# Power.net
KiCad netlist of a schematic drawn in Altium Designer
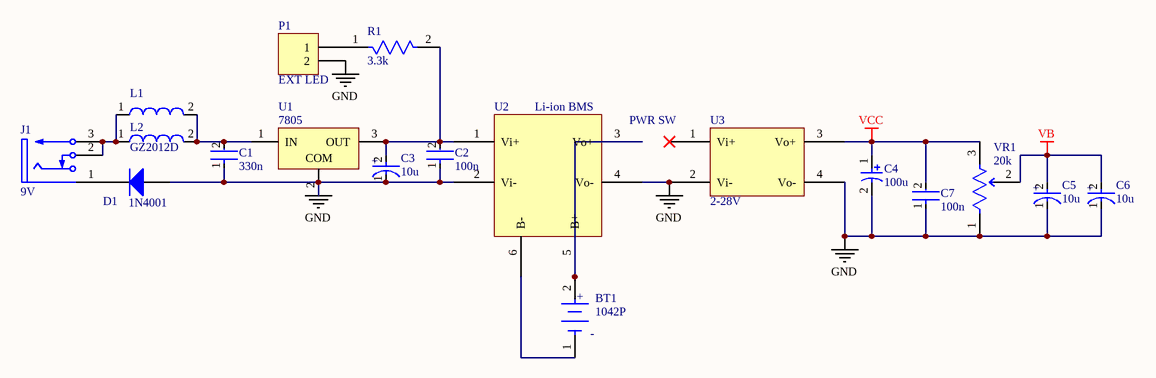
[diagram p0: Power.SchDoc]

(export (version "E")
  (design (tool "Eeschema 10.0.6"))
  (components
    (comp (ref "BT1")
      (value "1042P")
      (footprint "FP-1042P-MFG")
      (description "BATTERY HOLDER 18650 SMD TAB")
      (libsource (lib "Altium Content Vault") (part "60d3b5b901a8747834971d0eb8cf3fd"))
    )
    (comp (ref "C1")
      (value "330n")
      (footprint "FP-CL10-IPC_A")
      (description "Cap Ceramic 1nF 50V C0G ±5% Pad SMD 0603 +125°C T/R")
      (fields (field (name "VOLTAGE") "50V") (field (name "TOLERANCE") "5%"))
      (libsource (lib "Altium Content Vault") (part "b4654b650e69147ec39a6b967a45e02"))
    )
    (comp (ref "C2")
      (value "100n")
      (footprint "FP-CL10-IPC_A")
      (description "Cap Ceramic 1nF 50V C0G ±5% Pad SMD 0603 +125°C T/R")
      (fields (field (name "VOLTAGE") "50V") (field (name "TOLERANCE") "5%"))
      (libsource (lib "Altium Content Vault") (part "b4654b650e69147ec39a6b967a45e02"))
    )
    (comp (ref "C3")
      (value "10u")
      (footprint "FP-TAJA-MFG")
      (description "10uF 16V  ±10% 3Ω 1206  SMD Tantalum Capacitor")
      (fields (field (name "VOLTAGE") "16V") (field (name "TOLERANCE") "10%"))
      (libsource (lib "Altium Content Vault") (part "203bc49f2ac43e59fd269a8c329ed05"))
    )
    (comp (ref "C4") (value "100u") (footprint "EL_5X11_RA") (libsource (lib "TH_Symbols") (part "CAP_POL")))
    (comp (ref "C5")
      (value "10u")
      (footprint "FP-TAJA-MFG")
      (description "10uF 16V  ±10% 3Ω 1206  SMD Tantalum Capacitor")
      (fields (field (name "VOLTAGE") "16V") (field (name "TOLERANCE") "10%"))
      (libsource (lib "Altium Content Vault") (part "203bc49f2ac43e59fd269a8c329ed05"))
    )
    (comp (ref "C6")
      (value "10u")
      (footprint "FP-TAJA-MFG")
      (description "10uF 16V  ±10% 3Ω 1206  SMD Tantalum Capacitor")
      (fields (field (name "VOLTAGE") "16V") (field (name "TOLERANCE") "10%"))
      (libsource (lib "Altium Content Vault") (part "203bc49f2ac43e59fd269a8c329ed05"))
    )
    (comp (ref "C7")
      (value "100n")
      (footprint "FP-CL10-IPC_A")
      (description "Cap Ceramic 1nF 50V C0G ±5% Pad SMD 0603 +125°C T/R")
      (fields (field (name "VOLTAGE") "50V") (field (name "TOLERANCE") "5%"))
      (libsource (lib "Altium Content Vault") (part "b4654b650e69147ec39a6b967a45e02"))
    )
    (comp (ref "D1") (value "1N4001") (footprint "DO-41") (libsource (lib "TH_Symbols") (part "DIODE_SW")))
    (comp (ref "J1")
      (value "9V")
      (footprint "SWITCH-RAPC712X-3_V")
      (description "Power Jack, 5 A, 3-Pin THD, RoHS, Bulk")
      (fields (field (name "MANUFACTURER") "Switchcraft"))
      (libsource (lib "Altium Content Vault") (part "SWITCH-RAPC712X-3"))
    )
    (comp (ref "L1")
      (value "GZ2012D")
      (footprint "SMD-0805")
      (description "SMD EMI Suppression Ferrite Bead WE-CBF, Z = 1000 Ohm")
      (libsource (lib "Altium Content Vault") (part "PAS-IND-INDUCTOR-2"))
    )
    (comp (ref "L2")
      (value "GZ2012D")
      (footprint "SMD-0805")
      (description "SMD EMI Suppression Ferrite Bead WE-CBF, Z = 1000 Ohm")
      (libsource (lib "Altium Content Vault") (part "PAS-IND-INDUCTOR-2"))
    )
    (comp (ref "P1")
      (value "EXT LED")
      (footprint "HDR1X2")
      (description "Header, 2-Pin")
      (fields (field (name "PUBLISHER") "Altium Limited"))
      (libsource (lib "Miscellaneous Connectors") (part "Header 2"))
    )
    (comp (ref "R1")
      (value "3.3k")
      (footprint "FP-RT0805-MFG")
      (description "RES SMD 10K OHM 0.1% 1/8W 0805")
      (fields
        (field (name "MANUFACTURER PART NUMBER") "RT0805BRE0710KL")
        (field (name "MANUFACTURER") "Yageo")
      )
      (libsource (lib "Altium Content Vault") (part "1029c3af85768c4190bb7ad29bc67b5"))
    )
    (comp (ref "U1") (value "7805") (footprint "TO-220_H") (libsource (lib "TH_Symbols") (part "7805")))
    (comp (ref "U2") (value "Li-ion BMS") (footprint "BMS") (libsource (lib "TH_Symbols") (part "BMS")))
    (comp (ref "U3") (value "2-28V") (footprint "BOOST") (libsource (lib "TH_Symbols") (part "BOOST")))
    (comp (ref "VR1") (value "20k") (footprint "TRIM_6_TOP") (libsource (lib "TH_Symbols") (part "TRIM")))
  )
  (nets
    (net (code "1") (name "GND") (class "Default")
      (node (ref "C1") (pin "1") (pinfunction "1_1") (pintype "passive"))
      (node (ref "C2") (pin "1") (pinfunction "1_1") (pintype "passive"))
      (node (ref "C3") (pin "1") (pinfunction "C_1") (pintype "passive"))
      (node (ref "C4") (pin "2") (pinfunction "2_2") (pintype "passive"))
      (node (ref "C5") (pin "1") (pinfunction "C_1") (pintype "passive"))
      (node (ref "C6") (pin "1") (pinfunction "C_1") (pintype "passive"))
      (node (ref "C7") (pin "1") (pinfunction "1_1") (pintype "passive"))
      (node (ref "D1") (pin "1") (pinfunction "A_1") (pintype "passive"))
      (node (ref "P1") (pin "2") (pinfunction "2_2") (pintype "passive"))
      (node (ref "U1") (pin "2") (pinfunction "COM_2") (pintype "power_in"))
      (node (ref "U2") (pin "2") (pinfunction "Vi-_2") (pintype "passive"))
      (node (ref "U2") (pin "4") (pinfunction "Vo-_4") (pintype "passive"))
      (node (ref "U3") (pin "2") (pinfunction "Vi-_2") (pintype "passive"))
      (node (ref "U3") (pin "4") (pinfunction "Vo-_4") (pintype "passive"))
      (node (ref "VR1") (pin "1") (pinfunction "CCW_1") (pintype "passive"))
    )
    (net (code "2") (name "Net-(BT1-A)") (class "Default")
      (node (ref "BT1") (pin "2") (pinfunction "A_2") (pintype "passive"))
      (node (ref "U2") (pin "3") (pinfunction "Vo+_3") (pintype "passive"))
      (node (ref "U2") (pin "5") (pinfunction "B+_5") (pintype "passive"))
    )
    (net (code "3") (name "Net-(BT1-C)") (class "Default")
      (node (ref "BT1") (pin "1") (pinfunction "C_1") (pintype "passive"))
      (node (ref "U2") (pin "6") (pinfunction "B-_6") (pintype "passive"))
    )
    (net (code "4") (name "Net-(C3-A)") (class "Default")
      (node (ref "C2") (pin "2") (pinfunction "2_2") (pintype "passive"))
      (node (ref "C3") (pin "2") (pinfunction "A_2") (pintype "passive"))
      (node (ref "R1") (pin "2") (pinfunction "2_2") (pintype "passive"))
      (node (ref "U1") (pin "3") (pinfunction "OUT_3") (pintype "power_in"))
      (node (ref "U2") (pin "1") (pinfunction "Vi+_1") (pintype "passive"))
    )
    (net (code "5") (name "Net-(D1-K)") (class "Default")
      (node (ref "D1") (pin "2") (pinfunction "K_2") (pintype "passive"))
      (node (ref "J1") (pin "1") (pinfunction "1_1") (pintype "passive"))
    )
    (net (code "6") (name "Net-(J1-Pad2)") (class "Default")
      (node (ref "J1") (pin "2") (pinfunction "2_2") (pintype "passive"))
      (node (ref "J1") (pin "3") (pinfunction "3_3") (pintype "passive"))
      (node (ref "L1") (pin "1") (pinfunction "1_1") (pintype "passive"))
      (node (ref "L2") (pin "1") (pinfunction "1_1") (pintype "passive"))
    )
    (net (code "7") (name "Net-(P1-Pad1)") (class "Default")
      (node (ref "P1") (pin "1") (pinfunction "1_1") (pintype "passive"))
      (node (ref "R1") (pin "1") (pinfunction "1_1") (pintype "passive"))
    )
    (net (code "8") (name "Net-(U1-IN)") (class "Default")
      (node (ref "C1") (pin "2") (pinfunction "2_2") (pintype "passive"))
      (node (ref "L1") (pin "2") (pinfunction "2_2") (pintype "passive"))
      (node (ref "L2") (pin "2") (pinfunction "2_2") (pintype "passive"))
      (node (ref "U1") (pin "1") (pinfunction "IN_1") (pintype "power_in"))
    )
    (net (code "9") (name "VB") (class "Default")
      (node (ref "C5") (pin "2") (pinfunction "A_2") (pintype "passive"))
      (node (ref "C6") (pin "2") (pinfunction "A_2") (pintype "passive"))
      (node (ref "VR1") (pin "2") (pinfunction "WIPER_2") (pintype "passive"))
    )
    (net (code "10") (name "VCC") (class "Default")
      (node (ref "C4") (pin "1") (pinfunction "1_1") (pintype "passive"))
      (node (ref "C7") (pin "2") (pinfunction "2_2") (pintype "passive"))
      (node (ref "U3") (pin "3") (pinfunction "Vo+_3") (pintype "passive"))
      (node (ref "VR1") (pin "3") (pinfunction "CW_3") (pintype "passive"))
    )
    (net (code "11") (name "unconnected-(U3-Vi+-Pad1)") (class "Default")
      (node (ref "U3") (pin "1") (pinfunction "Vi+_1") (pintype "passive+no_connect"))
    )
  )
)
